# tarocco-v1.net
KiCad netlist of a schematic drawn in EAGLE
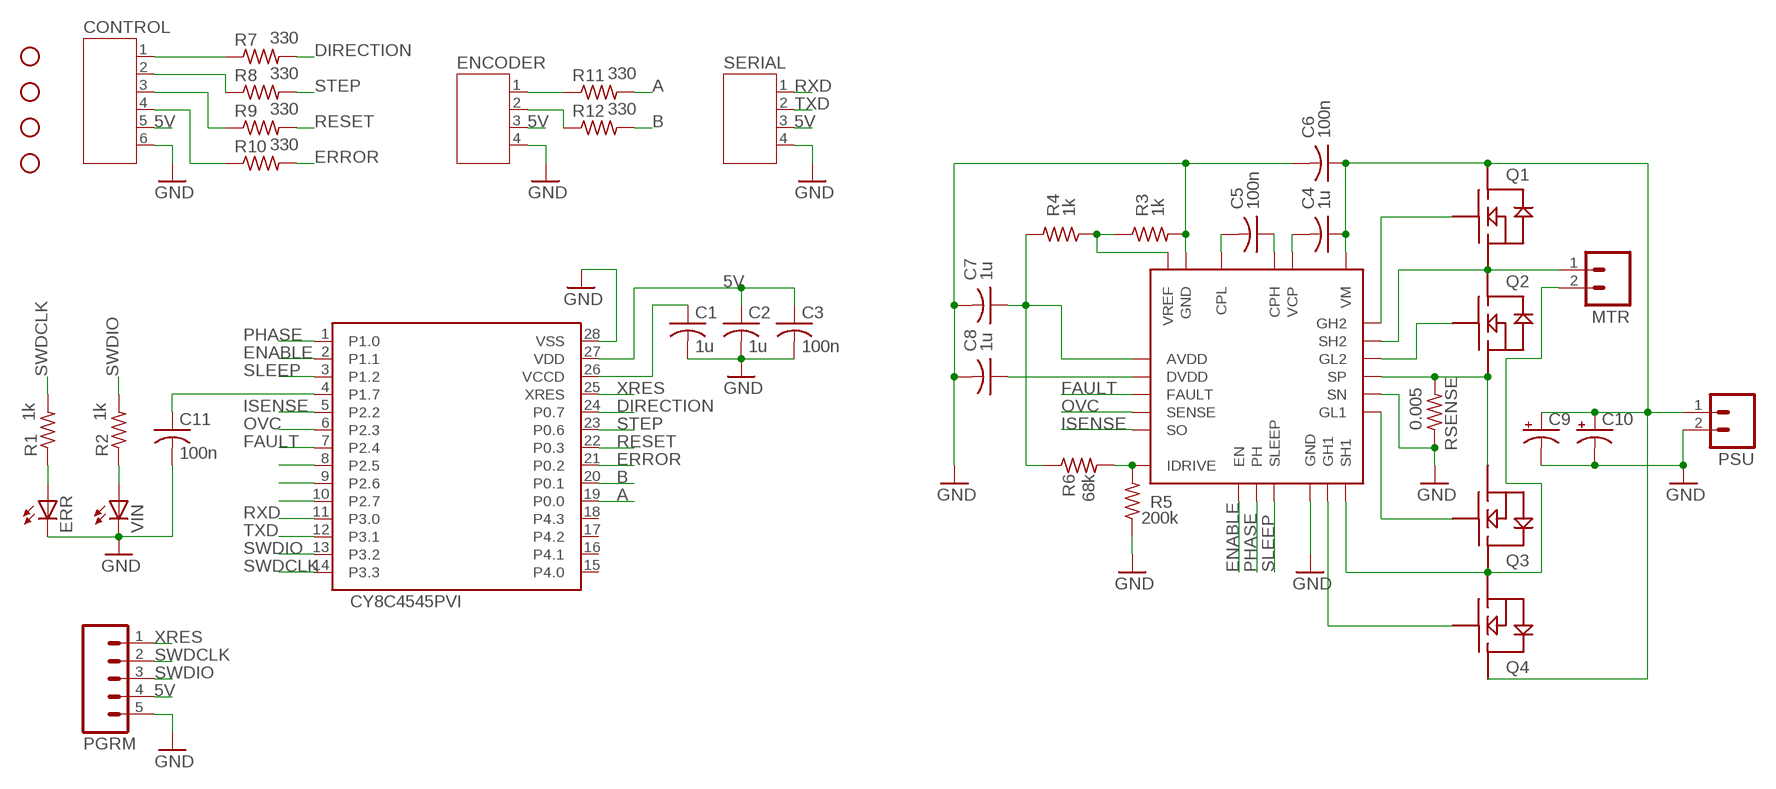
[diagram p0: schematic, sheet 1]

(export (version "E")
  (design (tool "Eeschema 10.0.6"))
  (components
    (comp (ref "8701")
      (value "DRV8701")
      (footprint "eagle-import:VQFN24")
      (libsource (lib "eagle-import") (part "DRV8701"))
    )
    (comp (ref "C1")
      (value "1u")
      (footprint "eagle-import:C0603")
      (libsource (lib "eagle-import") (part "C-USC0603"))
    )
    (comp (ref "C2")
      (value "1u")
      (footprint "eagle-import:C0603")
      (libsource (lib "eagle-import") (part "C-USC0603"))
    )
    (comp (ref "C3")
      (value "100n")
      (footprint "eagle-import:C0603")
      (libsource (lib "eagle-import") (part "C-USC0603"))
    )
    (comp (ref "C4")
      (value "1u")
      (footprint "eagle-import:C0603")
      (libsource (lib "eagle-import") (part "C-USC0603"))
    )
    (comp (ref "C5")
      (value "100n")
      (footprint "eagle-import:C0603")
      (libsource (lib "eagle-import") (part "C-USC0603"))
    )
    (comp (ref "C6")
      (value "100n")
      (footprint "eagle-import:C0603")
      (libsource (lib "eagle-import") (part "C-USC0603"))
    )
    (comp (ref "C7")
      (value "1u")
      (footprint "eagle-import:C0603")
      (libsource (lib "eagle-import") (part "C-USC0603"))
    )
    (comp (ref "C8")
      (value "1u")
      (footprint "eagle-import:C0603")
      (libsource (lib "eagle-import") (part "C-USC0603"))
    )
    (comp (ref "C9")
      (value "CPOL-USE3.5-8")
      (footprint "eagle-import:E3,5-8")
      (libsource (lib "eagle-import") (part "CPOL-USE3.5-8"))
    )
    (comp (ref "C10")
      (value "CPOL-USE3.5-8")
      (footprint "eagle-import:E3,5-8")
      (libsource (lib "eagle-import") (part "CPOL-USE3.5-8"))
    )
    (comp (ref "C11")
      (value "100n")
      (footprint "eagle-import:C0603")
      (libsource (lib "eagle-import") (part "C-USC0603"))
    )
    (comp (ref "CONTROL")
      (value "JST-PH6")
      (footprint "eagle-import:JST-PH6")
      (libsource (lib "eagle-import") (part "JST-PH6"))
    )
    (comp (ref "ENCODER")
      (value "JST-PH4")
      (footprint "eagle-import:JST-PH4")
      (libsource (lib "eagle-import") (part "JST-PH4"))
    )
    (comp (ref "ERR")
      (value "LEDCHIP-LED0603")
      (footprint "eagle-import:CHIP-LED0603")
      (libsource (lib "eagle-import") (part "LEDCHIP-LED0603"))
    )
    (comp (ref "IC1")
      (value "CY8C4545PVI")
      (footprint "eagle-import:SSOP28")
      (libsource (lib "eagle-import") (part "CY8C4545PVI"))
    )
    (comp (ref "MTR")
      (value "M023.5MM")
      (footprint "eagle-import:SCREWTERMINAL-3.5MM-2")
      (libsource (lib "eagle-import") (part "M023.5MM"))
    )
    (comp (ref "PGRM")
      (value "M05SMD2")
      (footprint "eagle-import:1X05-1MM-RA")
      (libsource (lib "eagle-import") (part "M05SMD2"))
    )
    (comp (ref "PSU")
      (value "M023.5MM")
      (footprint "eagle-import:SCREWTERMINAL-3.5MM-2")
      (libsource (lib "eagle-import") (part "M023.5MM"))
    )
    (comp (ref "Q1")
      (value "NEXFET_SINGLECSD18537NQ5A")
      (footprint "eagle-import:SON5X6")
      (libsource (lib "eagle-import") (part "NEXFET_SINGLECSD18537NQ5A"))
    )
    (comp (ref "Q2")
      (value "NEXFET_SINGLECSD18537NQ5A")
      (footprint "eagle-import:SON5X6")
      (libsource (lib "eagle-import") (part "NEXFET_SINGLECSD18537NQ5A"))
    )
    (comp (ref "Q3")
      (value "NEXFET_SINGLECSD18537NQ5A")
      (footprint "eagle-import:SON5X6")
      (libsource (lib "eagle-import") (part "NEXFET_SINGLECSD18537NQ5A"))
    )
    (comp (ref "Q4")
      (value "NEXFET_SINGLECSD18537NQ5A")
      (footprint "eagle-import:SON5X6")
      (libsource (lib "eagle-import") (part "NEXFET_SINGLECSD18537NQ5A"))
    )
    (comp (ref "R1")
      (value "1k")
      (footprint "eagle-import:R0603")
      (libsource (lib "eagle-import") (part "R-US_R0603"))
    )
    (comp (ref "R2")
      (value "1k")
      (footprint "eagle-import:R0603")
      (libsource (lib "eagle-import") (part "R-US_R0603"))
    )
    (comp (ref "R3")
      (value "1k")
      (footprint "eagle-import:R0603")
      (libsource (lib "eagle-import") (part "R-US_R0603"))
    )
    (comp (ref "R4")
      (value "1k")
      (footprint "eagle-import:R0603")
      (libsource (lib "eagle-import") (part "R-US_R0603"))
    )
    (comp (ref "R5")
      (value "200k")
      (footprint "eagle-import:R0603")
      (libsource (lib "eagle-import") (part "R-US_R0603"))
    )
    (comp (ref "R6")
      (value "68k")
      (footprint "eagle-import:R0603")
      (libsource (lib "eagle-import") (part "R-US_R0603"))
    )
    (comp (ref "R7")
      (value "330")
      (footprint "eagle-import:R0603")
      (libsource (lib "eagle-import") (part "R-US_R0603"))
    )
    (comp (ref "R8")
      (value "330")
      (footprint "eagle-import:R0603")
      (libsource (lib "eagle-import") (part "R-US_R0603"))
    )
    (comp (ref "R9")
      (value "330")
      (footprint "eagle-import:R0603")
      (libsource (lib "eagle-import") (part "R-US_R0603"))
    )
    (comp (ref "R10")
      (value "330")
      (footprint "eagle-import:R0603")
      (libsource (lib "eagle-import") (part "R-US_R0603"))
    )
    (comp (ref "R11")
      (value "330")
      (footprint "eagle-import:R0603")
      (libsource (lib "eagle-import") (part "R-US_R0603"))
    )
    (comp (ref "R12")
      (value "330")
      (footprint "eagle-import:R0603")
      (libsource (lib "eagle-import") (part "R-US_R0603"))
    )
    (comp (ref "RSENSE")
      (value "0.005")
      (footprint "eagle-import:R2512")
      (libsource (lib "eagle-import") (part "R-US_R2512"))
    )
    (comp (ref "SERIAL")
      (value "JST-PH4")
      (footprint "eagle-import:JST-PH4")
      (libsource (lib "eagle-import") (part "JST-PH4"))
    )
    (comp (ref "STANDOFF1")
      (value "STAND-OFF")
      (footprint "eagle-import:STAND-OFF")
      (libsource (lib "eagle-import") (part "STAND-OFF"))
    )
    (comp (ref "STANDOFF2")
      (value "STAND-OFF")
      (footprint "eagle-import:STAND-OFF")
      (libsource (lib "eagle-import") (part "STAND-OFF"))
    )
    (comp (ref "STANDOFF3")
      (value "STAND-OFF")
      (footprint "eagle-import:STAND-OFF")
      (libsource (lib "eagle-import") (part "STAND-OFF"))
    )
    (comp (ref "STANDOFF4")
      (value "STAND-OFF")
      (footprint "eagle-import:STAND-OFF")
      (libsource (lib "eagle-import") (part "STAND-OFF"))
    )
    (comp (ref "VIN")
      (value "LEDCHIP-LED0603")
      (footprint "eagle-import:CHIP-LED0603")
      (libsource (lib "eagle-import") (part "LEDCHIP-LED0603"))
    )
  )
  (nets
    (net (code "1") (name "/5V") (class "Default")
      (node (ref "C2") (pin "1") (pinfunction "1_1") (pintype "passive"))
      (node (ref "C3") (pin "1") (pinfunction "1_1") (pintype "passive"))
      (node (ref "CONTROL") (pin "5") (pinfunction "5_5") (pintype "passive"))
      (node (ref "ENCODER") (pin "3") (pinfunction "3_3") (pintype "passive"))
      (node (ref "IC1") (pin "27") (pinfunction "VDD_27") (pintype "power_in"))
      (node (ref "PGRM") (pin "4") (pinfunction "4_4") (pintype "passive"))
      (node (ref "SERIAL") (pin "3") (pinfunction "3_3") (pintype "passive"))
    )
    (net (code "2") (name "/A") (class "Default")
      (node (ref "IC1") (pin "19") (pinfunction "P0.0_19") (pintype "bidirectional"))
      (node (ref "R11") (pin "2") (pinfunction "2_2") (pintype "passive"))
    )
    (net (code "3") (name "/B") (class "Default")
      (node (ref "IC1") (pin "20") (pinfunction "P0.1_20") (pintype "bidirectional"))
      (node (ref "R12") (pin "2") (pinfunction "2_2") (pintype "passive"))
    )
    (net (code "4") (name "/DIRECTION") (class "Default")
      (node (ref "IC1") (pin "24") (pinfunction "P0.7_24") (pintype "bidirectional"))
      (node (ref "R7") (pin "2") (pinfunction "2_2") (pintype "passive"))
    )
    (net (code "5") (name "/ENABLE") (class "Default")
      (node (ref "8701") (pin "EN") (pinfunction "EN_EN") (pintype "bidirectional"))
      (node (ref "IC1") (pin "2") (pinfunction "P1.1_2") (pintype "bidirectional"))
    )
    (net (code "6") (name "/ERROR") (class "Default")
      (node (ref "IC1") (pin "21") (pinfunction "P0.2_21") (pintype "bidirectional"))
      (node (ref "R10") (pin "2") (pinfunction "2_2") (pintype "passive"))
    )
    (net (code "7") (name "/FAULT") (class "Default")
      (node (ref "8701") (pin "FAULT") (pinfunction "FAULT_FAULT") (pintype "bidirectional"))
      (node (ref "IC1") (pin "7") (pinfunction "P2.4_7") (pintype "bidirectional"))
    )
    (net (code "8") (name "/ISENSE") (class "Default")
      (node (ref "8701") (pin "SO") (pinfunction "SO_SO") (pintype "bidirectional"))
      (node (ref "IC1") (pin "5") (pinfunction "P2.2_5") (pintype "bidirectional"))
    )
    (net (code "9") (name "/OVC") (class "Default")
      (node (ref "8701") (pin "SENSE") (pinfunction "SENSE_SENSE") (pintype "bidirectional"))
      (node (ref "IC1") (pin "6") (pinfunction "P2.3_6") (pintype "bidirectional"))
    )
    (net (code "10") (name "/PHASE") (class "Default")
      (node (ref "8701") (pin "PH") (pinfunction "PH_PH") (pintype "bidirectional"))
      (node (ref "IC1") (pin "1") (pinfunction "P1.0_1") (pintype "bidirectional"))
    )
    (net (code "11") (name "/RESET") (class "Default")
      (node (ref "IC1") (pin "22") (pinfunction "P0.3_22") (pintype "bidirectional"))
      (node (ref "R9") (pin "2") (pinfunction "2_2") (pintype "passive"))
    )
    (net (code "12") (name "/RXD") (class "Default")
      (node (ref "IC1") (pin "11") (pinfunction "P3.0_11") (pintype "bidirectional"))
      (node (ref "SERIAL") (pin "1") (pinfunction "1_1") (pintype "passive"))
    )
    (net (code "13") (name "/SLEEP") (class "Default")
      (node (ref "8701") (pin "SLEEP") (pinfunction "SLEEP_SLEEP") (pintype "bidirectional"))
      (node (ref "IC1") (pin "3") (pinfunction "P1.2_3") (pintype "bidirectional"))
    )
    (net (code "14") (name "/STEP") (class "Default")
      (node (ref "IC1") (pin "23") (pinfunction "P0.6_23") (pintype "bidirectional"))
      (node (ref "R8") (pin "2") (pinfunction "2_2") (pintype "passive"))
    )
    (net (code "15") (name "/SWDCLK") (class "Default")
      (node (ref "IC1") (pin "14") (pinfunction "P3.3_14") (pintype "bidirectional"))
      (node (ref "PGRM") (pin "2") (pinfunction "2_2") (pintype "passive"))
      (node (ref "R1") (pin "2") (pinfunction "2_2") (pintype "passive"))
    )
    (net (code "16") (name "/SWDIO") (class "Default")
      (node (ref "IC1") (pin "13") (pinfunction "P3.2_13") (pintype "bidirectional"))
      (node (ref "PGRM") (pin "3") (pinfunction "3_3") (pintype "passive"))
      (node (ref "R2") (pin "2") (pinfunction "2_2") (pintype "passive"))
    )
    (net (code "17") (name "/TXD") (class "Default")
      (node (ref "IC1") (pin "12") (pinfunction "P3.1_12") (pintype "bidirectional"))
      (node (ref "SERIAL") (pin "2") (pinfunction "2_2") (pintype "passive"))
    )
    (net (code "18") (name "/XRES") (class "Default")
      (node (ref "IC1") (pin "25") (pinfunction "XRES_25") (pintype "bidirectional"))
      (node (ref "PGRM") (pin "1") (pinfunction "1_1") (pintype "passive"))
    )
    (net (code "19") (name "GND") (class "Default")
      (node (ref "8701") (pin "GND@1") (pinfunction "GND_GND@1") (pintype "bidirectional"))
      (node (ref "8701") (pin "GND@2") (pinfunction "GND_GND@2") (pintype "bidirectional"))
      (node (ref "8701") (pin "GND@3") (pinfunction "GND_GND@3") (pintype "bidirectional"))
      (node (ref "8701") (pin "SN") (pinfunction "SN_SN") (pintype "bidirectional"))
      (node (ref "C1") (pin "2") (pinfunction "2_2") (pintype "passive"))
      (node (ref "C10") (pin "-") (pinfunction "-_-") (pintype "passive"))
      (node (ref "C11") (pin "2") (pinfunction "2_2") (pintype "passive"))
      (node (ref "C2") (pin "2") (pinfunction "2_2") (pintype "passive"))
      (node (ref "C3") (pin "2") (pinfunction "2_2") (pintype "passive"))
      (node (ref "C6") (pin "2") (pinfunction "2_2") (pintype "passive"))
      (node (ref "C7") (pin "2") (pinfunction "2_2") (pintype "passive"))
      (node (ref "C8") (pin "2") (pinfunction "2_2") (pintype "passive"))
      (node (ref "C9") (pin "-") (pinfunction "-_-") (pintype "passive"))
      (node (ref "CONTROL") (pin "6") (pinfunction "6_6") (pintype "passive"))
      (node (ref "ENCODER") (pin "4") (pinfunction "4_4") (pintype "passive"))
      (node (ref "ERR") (pin "C") (pinfunction "C_C") (pintype "passive"))
      (node (ref "IC1") (pin "28") (pinfunction "VSS_28") (pintype "power_in"))
      (node (ref "PGRM") (pin "5") (pinfunction "5_5") (pintype "passive"))
      (node (ref "PSU") (pin "2") (pinfunction "2_2") (pintype "passive"))
      (node (ref "R3") (pin "2") (pinfunction "2_2") (pintype "passive"))
      (node (ref "R5") (pin "1") (pinfunction "1_1") (pintype "passive"))
      (node (ref "RSENSE") (pin "1") (pinfunction "1_1") (pintype "passive"))
      (node (ref "SERIAL") (pin "4") (pinfunction "4_4") (pintype "passive"))
      (node (ref "VIN") (pin "C") (pinfunction "C_C") (pintype "passive"))
    )
    (net (code "20") (name "Net-(8701-PadAVDD)") (class "Default")
      (node (ref "8701") (pin "AVDD") (pinfunction "AVDD_AVDD") (pintype "bidirectional"))
      (node (ref "C7") (pin "1") (pinfunction "1_1") (pintype "passive"))
      (node (ref "R4") (pin "2") (pinfunction "2_2") (pintype "passive"))
      (node (ref "R6") (pin "1") (pinfunction "1_1") (pintype "passive"))
    )
    (net (code "21") (name "Net-(8701-PadCPH)") (class "Default")
      (node (ref "8701") (pin "CPH") (pinfunction "CPH_CPH") (pintype "bidirectional"))
      (node (ref "C5") (pin "1") (pinfunction "1_1") (pintype "passive"))
    )
    (net (code "22") (name "Net-(8701-PadCPL)") (class "Default")
      (node (ref "8701") (pin "CPL") (pinfunction "CPL_CPL") (pintype "bidirectional"))
      (node (ref "C5") (pin "2") (pinfunction "2_2") (pintype "passive"))
    )
    (net (code "23") (name "Net-(8701-PadDVDD)") (class "Default")
      (node (ref "8701") (pin "DVDD") (pinfunction "DVDD_DVDD") (pintype "bidirectional"))
      (node (ref "C8") (pin "1") (pinfunction "1_1") (pintype "passive"))
    )
    (net (code "24") (name "Net-(8701-PadGH1)") (class "Default")
      (node (ref "8701") (pin "GH1") (pinfunction "GH1_GH1") (pintype "bidirectional"))
      (node (ref "Q4") (pin "GATE") (pinfunction "GATE_GATE") (pintype "bidirectional"))
    )
    (net (code "25") (name "Net-(8701-PadGH2)") (class "Default")
      (node (ref "8701") (pin "GH2") (pinfunction "GH2_GH2") (pintype "bidirectional"))
      (node (ref "Q1") (pin "GATE") (pinfunction "GATE_GATE") (pintype "bidirectional"))
    )
    (net (code "26") (name "Net-(8701-PadGL1)") (class "Default")
      (node (ref "8701") (pin "GL1") (pinfunction "GL1_GL1") (pintype "bidirectional"))
      (node (ref "Q3") (pin "GATE") (pinfunction "GATE_GATE") (pintype "bidirectional"))
    )
    (net (code "27") (name "Net-(8701-PadGL2)") (class "Default")
      (node (ref "8701") (pin "GL2") (pinfunction "GL2_GL2") (pintype "bidirectional"))
      (node (ref "Q2") (pin "GATE") (pinfunction "GATE_GATE") (pintype "bidirectional"))
    )
    (net (code "28") (name "Net-(8701-PadIDRIVE)") (class "Default")
      (node (ref "8701") (pin "IDRIVE") (pinfunction "IDRIVE_IDRIVE") (pintype "bidirectional"))
      (node (ref "R5") (pin "2") (pinfunction "2_2") (pintype "passive"))
      (node (ref "R6") (pin "2") (pinfunction "2_2") (pintype "passive"))
    )
    (net (code "29") (name "Net-(8701-PadSH1)") (class "Default")
      (node (ref "8701") (pin "SH1") (pinfunction "SH1_SH1") (pintype "bidirectional"))
      (node (ref "MTR") (pin "2") (pinfunction "2_2") (pintype "passive"))
      (node (ref "Q3") (pin "DRAIN@1") (pinfunction "DRAIN_DRAIN@1") (pintype "bidirectional"))
      (node (ref "Q3") (pin "DRAIN@2") (pinfunction "DRAIN_DRAIN@2") (pintype "bidirectional"))
      (node (ref "Q3") (pin "DRAIN@3") (pinfunction "DRAIN_DRAIN@3") (pintype "bidirectional"))
      (node (ref "Q3") (pin "DRAIN@4") (pinfunction "DRAIN_DRAIN@4") (pintype "bidirectional"))
      (node (ref "Q3") (pin "DRAIN@5") (pinfunction "DRAIN_DRAIN@5") (pintype "bidirectional"))
      (node (ref "Q4") (pin "SOURCE@1") (pinfunction "SOURCE_SOURCE@1") (pintype "bidirectional"))
      (node (ref "Q4") (pin "SOURCE@2") (pinfunction "SOURCE_SOURCE@2") (pintype "bidirectional"))
      (node (ref "Q4") (pin "SOURCE@3") (pinfunction "SOURCE_SOURCE@3") (pintype "bidirectional"))
    )
    (net (code "30") (name "Net-(8701-PadSH2)") (class "Default")
      (node (ref "8701") (pin "SH2") (pinfunction "SH2_SH2") (pintype "bidirectional"))
      (node (ref "MTR") (pin "1") (pinfunction "1_1") (pintype "passive"))
      (node (ref "Q1") (pin "SOURCE@1") (pinfunction "SOURCE_SOURCE@1") (pintype "bidirectional"))
      (node (ref "Q1") (pin "SOURCE@2") (pinfunction "SOURCE_SOURCE@2") (pintype "bidirectional"))
      (node (ref "Q1") (pin "SOURCE@3") (pinfunction "SOURCE_SOURCE@3") (pintype "bidirectional"))
      (node (ref "Q2") (pin "DRAIN@1") (pinfunction "DRAIN_DRAIN@1") (pintype "bidirectional"))
      (node (ref "Q2") (pin "DRAIN@2") (pinfunction "DRAIN_DRAIN@2") (pintype "bidirectional"))
      (node (ref "Q2") (pin "DRAIN@3") (pinfunction "DRAIN_DRAIN@3") (pintype "bidirectional"))
      (node (ref "Q2") (pin "DRAIN@4") (pinfunction "DRAIN_DRAIN@4") (pintype "bidirectional"))
      (node (ref "Q2") (pin "DRAIN@5") (pinfunction "DRAIN_DRAIN@5") (pintype "bidirectional"))
    )
    (net (code "31") (name "Net-(8701-PadSP)") (class "Default")
      (node (ref "8701") (pin "SP") (pinfunction "SP_SP") (pintype "bidirectional"))
      (node (ref "Q2") (pin "SOURCE@1") (pinfunction "SOURCE_SOURCE@1") (pintype "bidirectional"))
      (node (ref "Q2") (pin "SOURCE@2") (pinfunction "SOURCE_SOURCE@2") (pintype "bidirectional"))
      (node (ref "Q2") (pin "SOURCE@3") (pinfunction "SOURCE_SOURCE@3") (pintype "bidirectional"))
      (node (ref "Q3") (pin "SOURCE@1") (pinfunction "SOURCE_SOURCE@1") (pintype "bidirectional"))
      (node (ref "Q3") (pin "SOURCE@2") (pinfunction "SOURCE_SOURCE@2") (pintype "bidirectional"))
      (node (ref "Q3") (pin "SOURCE@3") (pinfunction "SOURCE_SOURCE@3") (pintype "bidirectional"))
      (node (ref "RSENSE") (pin "2") (pinfunction "2_2") (pintype "passive"))
    )
    (net (code "32") (name "Net-(8701-PadVCP)") (class "Default")
      (node (ref "8701") (pin "VCP") (pinfunction "VCP_VCP") (pintype "bidirectional"))
      (node (ref "C4") (pin "2") (pinfunction "2_2") (pintype "passive"))
    )
    (net (code "33") (name "Net-(8701-PadVM)") (class "Default")
      (node (ref "8701") (pin "VM") (pinfunction "VM_VM") (pintype "bidirectional"))
      (node (ref "C10") (pin "+") (pinfunction "+_+") (pintype "passive"))
      (node (ref "C4") (pin "1") (pinfunction "1_1") (pintype "passive"))
      (node (ref "C6") (pin "1") (pinfunction "1_1") (pintype "passive"))
      (node (ref "C9") (pin "+") (pinfunction "+_+") (pintype "passive"))
      (node (ref "PSU") (pin "1") (pinfunction "1_1") (pintype "passive"))
      (node (ref "Q1") (pin "DRAIN@1") (pinfunction "DRAIN_DRAIN@1") (pintype "bidirectional"))
      (node (ref "Q1") (pin "DRAIN@2") (pinfunction "DRAIN_DRAIN@2") (pintype "bidirectional"))
      (node (ref "Q1") (pin "DRAIN@3") (pinfunction "DRAIN_DRAIN@3") (pintype "bidirectional"))
      (node (ref "Q1") (pin "DRAIN@4") (pinfunction "DRAIN_DRAIN@4") (pintype "bidirectional"))
      (node (ref "Q1") (pin "DRAIN@5") (pinfunction "DRAIN_DRAIN@5") (pintype "bidirectional"))
      (node (ref "Q4") (pin "DRAIN@1") (pinfunction "DRAIN_DRAIN@1") (pintype "bidirectional"))
      (node (ref "Q4") (pin "DRAIN@2") (pinfunction "DRAIN_DRAIN@2") (pintype "bidirectional"))
      (node (ref "Q4") (pin "DRAIN@3") (pinfunction "DRAIN_DRAIN@3") (pintype "bidirectional"))
      (node (ref "Q4") (pin "DRAIN@4") (pinfunction "DRAIN_DRAIN@4") (pintype "bidirectional"))
      (node (ref "Q4") (pin "DRAIN@5") (pinfunction "DRAIN_DRAIN@5") (pintype "bidirectional"))
    )
    (net (code "34") (name "Net-(8701-PadVREF)") (class "Default")
      (node (ref "8701") (pin "VREF") (pinfunction "VREF_VREF") (pintype "bidirectional"))
      (node (ref "R3") (pin "1") (pinfunction "1_1") (pintype "passive"))
      (node (ref "R4") (pin "1") (pinfunction "1_1") (pintype "passive"))
    )
    (net (code "35") (name "Net-(CONTROL-Pad1)") (class "Default")
      (node (ref "CONTROL") (pin "1") (pinfunction "1_1") (pintype "passive"))
      (node (ref "R7") (pin "1") (pinfunction "1_1") (pintype "passive"))
    )
    (net (code "36") (name "Net-(CONTROL-Pad2)") (class "Default")
      (node (ref "CONTROL") (pin "2") (pinfunction "2_2") (pintype "passive"))
      (node (ref "R8") (pin "1") (pinfunction "1_1") (pintype "passive"))
    )
    (net (code "37") (name "Net-(CONTROL-Pad3)") (class "Default")
      (node (ref "CONTROL") (pin "3") (pinfunction "3_3") (pintype "passive"))
      (node (ref "R9") (pin "1") (pinfunction "1_1") (pintype "passive"))
    )
    (net (code "38") (name "Net-(CONTROL-Pad4)") (class "Default")
      (node (ref "CONTROL") (pin "4") (pinfunction "4_4") (pintype "passive"))
      (node (ref "R10") (pin "1") (pinfunction "1_1") (pintype "passive"))
    )
    (net (code "39") (name "Net-(ENCODER-Pad1)") (class "Default")
      (node (ref "ENCODER") (pin "1") (pinfunction "1_1") (pintype "passive"))
      (node (ref "R11") (pin "1") (pinfunction "1_1") (pintype "passive"))
    )
    (net (code "40") (name "Net-(ENCODER-Pad2)") (class "Default")
      (node (ref "ENCODER") (pin "2") (pinfunction "2_2") (pintype "passive"))
      (node (ref "R12") (pin "1") (pinfunction "1_1") (pintype "passive"))
    )
    (net (code "41") (name "Net-(ERR-PadA)") (class "Default")
      (node (ref "ERR") (pin "A") (pinfunction "A_A") (pintype "passive"))
      (node (ref "R1") (pin "1") (pinfunction "1_1") (pintype "passive"))
    )
    (net (code "42") (name "Net-(IC1-P1.7)") (class "Default")
      (node (ref "C11") (pin "1") (pinfunction "1_1") (pintype "passive"))
      (node (ref "IC1") (pin "4") (pinfunction "P1.7_4") (pintype "bidirectional"))
    )
    (net (code "43") (name "Net-(IC1-VCCD)") (class "Default")
      (node (ref "C1") (pin "1") (pinfunction "1_1") (pintype "passive"))
      (node (ref "IC1") (pin "26") (pinfunction "VCCD_26") (pintype "power_in"))
    )
    (net (code "44") (name "Net-(R2-Pad1)") (class "Default")
      (node (ref "R2") (pin "1") (pinfunction "1_1") (pintype "passive"))
      (node (ref "VIN") (pin "A") (pinfunction "A_A") (pintype "passive"))
    )
    (net (code "45") (name "unconnected-(IC1-P2.5-Pad8)") (class "Default")
      (node (ref "IC1") (pin "8") (pinfunction "P2.5_8") (pintype "bidirectional"))
    )
    (net (code "46") (name "unconnected-(IC1-P2.6-Pad9)") (class "Default")
      (node (ref "IC1") (pin "9") (pinfunction "P2.6_9") (pintype "bidirectional"))
    )
    (net (code "47") (name "unconnected-(IC1-P2.7-Pad10)") (class "Default")
      (node (ref "IC1") (pin "10") (pinfunction "P2.7_10") (pintype "bidirectional"))
    )
    (net (code "48") (name "unconnected-(IC1-P4.0-Pad15)") (class "Default")
      (node (ref "IC1") (pin "15") (pinfunction "P4.0_15") (pintype "bidirectional"))
    )
    (net (code "49") (name "unconnected-(IC1-P4.1-Pad16)") (class "Default")
      (node (ref "IC1") (pin "16") (pinfunction "P4.1_16") (pintype "bidirectional"))
    )
    (net (code "50") (name "unconnected-(IC1-P4.2-Pad17)") (class "Default")
      (node (ref "IC1") (pin "17") (pinfunction "P4.2_17") (pintype "bidirectional"))
    )
    (net (code "51") (name "unconnected-(IC1-P4.3-Pad18)") (class "Default")
      (node (ref "IC1") (pin "18") (pinfunction "P4.3_18") (pintype "bidirectional"))
    )
  )
)
